# GarageDigitalClockDisplay.net
KiCad netlist of a schematic drawn in EAGLE
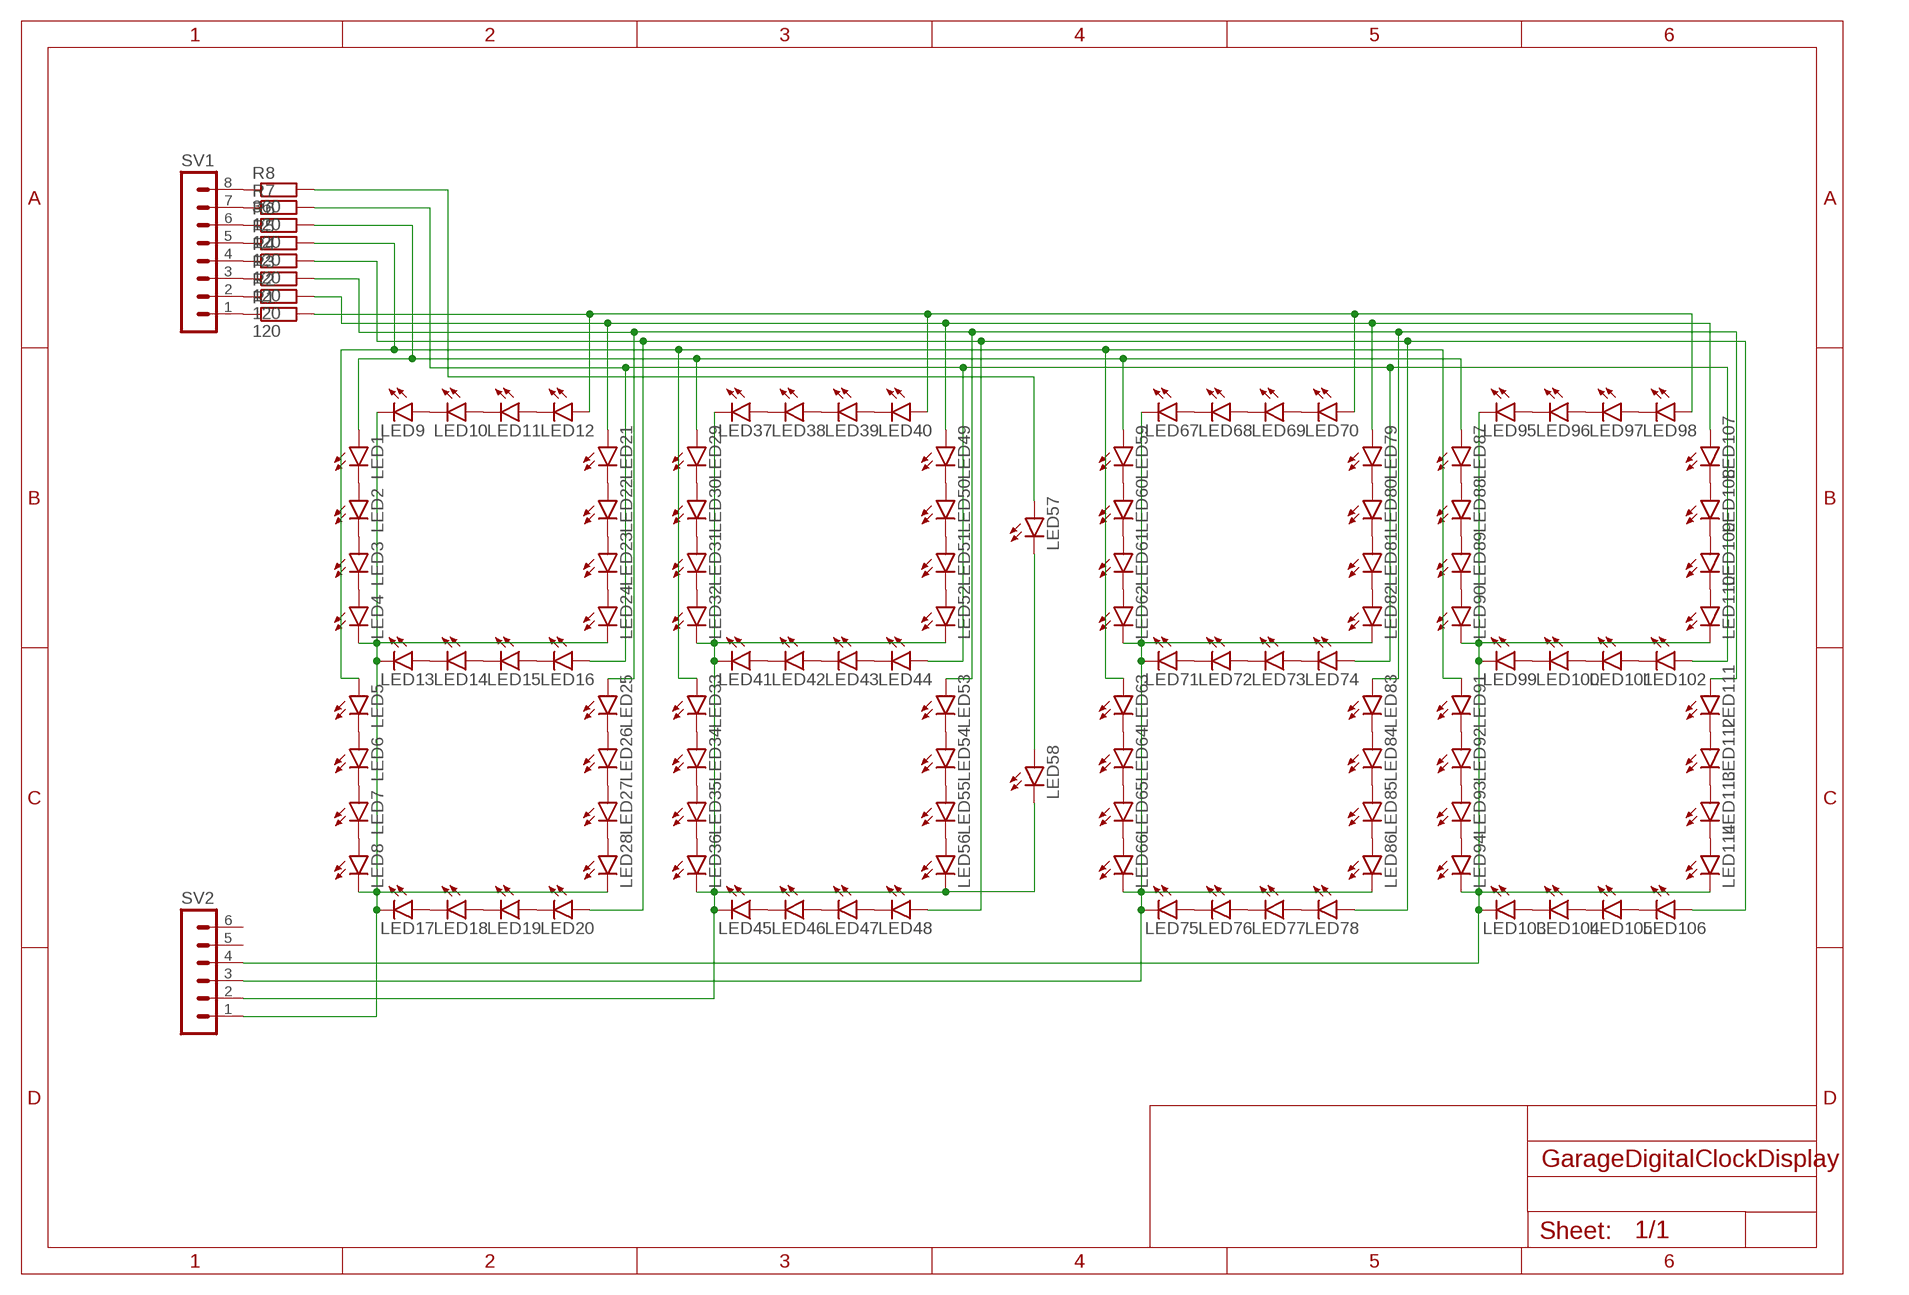
[diagram p0: schematic, sheet 1]

(export (version "E")
  (design (tool "Eeschema 10.0.6"))
  (components
    (comp (ref "LED1")
      (value "LED5MM")
      (footprint "eagle-import:LED5MM")
      (libsource (lib "eagle-import") (part "LED5MM"))
    )
    (comp (ref "LED2")
      (value "LED5MM")
      (footprint "eagle-import:LED5MM")
      (libsource (lib "eagle-import") (part "LED5MM"))
    )
    (comp (ref "LED3")
      (value "LED5MM")
      (footprint "eagle-import:LED5MM")
      (libsource (lib "eagle-import") (part "LED5MM"))
    )
    (comp (ref "LED4")
      (value "LED5MM")
      (footprint "eagle-import:LED5MM")
      (libsource (lib "eagle-import") (part "LED5MM"))
    )
    (comp (ref "LED5")
      (value "LED5MM")
      (footprint "eagle-import:LED5MM")
      (libsource (lib "eagle-import") (part "LED5MM"))
    )
    (comp (ref "LED6")
      (value "LED5MM")
      (footprint "eagle-import:LED5MM")
      (libsource (lib "eagle-import") (part "LED5MM"))
    )
    (comp (ref "LED7")
      (value "LED5MM")
      (footprint "eagle-import:LED5MM")
      (libsource (lib "eagle-import") (part "LED5MM"))
    )
    (comp (ref "LED8")
      (value "LED5MM")
      (footprint "eagle-import:LED5MM")
      (libsource (lib "eagle-import") (part "LED5MM"))
    )
    (comp (ref "LED9")
      (value "LED5MM")
      (footprint "eagle-import:LED5MM")
      (libsource (lib "eagle-import") (part "LED5MM"))
    )
    (comp (ref "LED10")
      (value "LED5MM")
      (footprint "eagle-import:LED5MM")
      (libsource (lib "eagle-import") (part "LED5MM"))
    )
    (comp (ref "LED11")
      (value "LED5MM")
      (footprint "eagle-import:LED5MM")
      (libsource (lib "eagle-import") (part "LED5MM"))
    )
    (comp (ref "LED12")
      (value "LED5MM")
      (footprint "eagle-import:LED5MM")
      (libsource (lib "eagle-import") (part "LED5MM"))
    )
    (comp (ref "LED13")
      (value "LED5MM")
      (footprint "eagle-import:LED5MM")
      (libsource (lib "eagle-import") (part "LED5MM"))
    )
    (comp (ref "LED14")
      (value "LED5MM")
      (footprint "eagle-import:LED5MM")
      (libsource (lib "eagle-import") (part "LED5MM"))
    )
    (comp (ref "LED15")
      (value "LED5MM")
      (footprint "eagle-import:LED5MM")
      (libsource (lib "eagle-import") (part "LED5MM"))
    )
    (comp (ref "LED16")
      (value "LED5MM")
      (footprint "eagle-import:LED5MM")
      (libsource (lib "eagle-import") (part "LED5MM"))
    )
    (comp (ref "LED17")
      (value "LED5MM")
      (footprint "eagle-import:LED5MM")
      (libsource (lib "eagle-import") (part "LED5MM"))
    )
    (comp (ref "LED18")
      (value "LED5MM")
      (footprint "eagle-import:LED5MM")
      (libsource (lib "eagle-import") (part "LED5MM"))
    )
    (comp (ref "LED19")
      (value "LED5MM")
      (footprint "eagle-import:LED5MM")
      (libsource (lib "eagle-import") (part "LED5MM"))
    )
    (comp (ref "LED20")
      (value "LED5MM")
      (footprint "eagle-import:LED5MM")
      (libsource (lib "eagle-import") (part "LED5MM"))
    )
    (comp (ref "LED21")
      (value "LED5MM")
      (footprint "eagle-import:LED5MM")
      (libsource (lib "eagle-import") (part "LED5MM"))
    )
    (comp (ref "LED22")
      (value "LED5MM")
      (footprint "eagle-import:LED5MM")
      (libsource (lib "eagle-import") (part "LED5MM"))
    )
    (comp (ref "LED23")
      (value "LED5MM")
      (footprint "eagle-import:LED5MM")
      (libsource (lib "eagle-import") (part "LED5MM"))
    )
    (comp (ref "LED24")
      (value "LED5MM")
      (footprint "eagle-import:LED5MM")
      (libsource (lib "eagle-import") (part "LED5MM"))
    )
    (comp (ref "LED25")
      (value "LED5MM")
      (footprint "eagle-import:LED5MM")
      (libsource (lib "eagle-import") (part "LED5MM"))
    )
    (comp (ref "LED26")
      (value "LED5MM")
      (footprint "eagle-import:LED5MM")
      (libsource (lib "eagle-import") (part "LED5MM"))
    )
    (comp (ref "LED27")
      (value "LED5MM")
      (footprint "eagle-import:LED5MM")
      (libsource (lib "eagle-import") (part "LED5MM"))
    )
    (comp (ref "LED28")
      (value "LED5MM")
      (footprint "eagle-import:LED5MM")
      (libsource (lib "eagle-import") (part "LED5MM"))
    )
    (comp (ref "LED29")
      (value "LED5MM")
      (footprint "eagle-import:LED5MM")
      (libsource (lib "eagle-import") (part "LED5MM"))
    )
    (comp (ref "LED30")
      (value "LED5MM")
      (footprint "eagle-import:LED5MM")
      (libsource (lib "eagle-import") (part "LED5MM"))
    )
    (comp (ref "LED31")
      (value "LED5MM")
      (footprint "eagle-import:LED5MM")
      (libsource (lib "eagle-import") (part "LED5MM"))
    )
    (comp (ref "LED32")
      (value "LED5MM")
      (footprint "eagle-import:LED5MM")
      (libsource (lib "eagle-import") (part "LED5MM"))
    )
    (comp (ref "LED33")
      (value "LED5MM")
      (footprint "eagle-import:LED5MM")
      (libsource (lib "eagle-import") (part "LED5MM"))
    )
    (comp (ref "LED34")
      (value "LED5MM")
      (footprint "eagle-import:LED5MM")
      (libsource (lib "eagle-import") (part "LED5MM"))
    )
    (comp (ref "LED35")
      (value "LED5MM")
      (footprint "eagle-import:LED5MM")
      (libsource (lib "eagle-import") (part "LED5MM"))
    )
    (comp (ref "LED36")
      (value "LED5MM")
      (footprint "eagle-import:LED5MM")
      (libsource (lib "eagle-import") (part "LED5MM"))
    )
    (comp (ref "LED37")
      (value "LED5MM")
      (footprint "eagle-import:LED5MM")
      (libsource (lib "eagle-import") (part "LED5MM"))
    )
    (comp (ref "LED38")
      (value "LED5MM")
      (footprint "eagle-import:LED5MM")
      (libsource (lib "eagle-import") (part "LED5MM"))
    )
    (comp (ref "LED39")
      (value "LED5MM")
      (footprint "eagle-import:LED5MM")
      (libsource (lib "eagle-import") (part "LED5MM"))
    )
    (comp (ref "LED40")
      (value "LED5MM")
      (footprint "eagle-import:LED5MM")
      (libsource (lib "eagle-import") (part "LED5MM"))
    )
    (comp (ref "LED41")
      (value "LED5MM")
      (footprint "eagle-import:LED5MM")
      (libsource (lib "eagle-import") (part "LED5MM"))
    )
    (comp (ref "LED42")
      (value "LED5MM")
      (footprint "eagle-import:LED5MM")
      (libsource (lib "eagle-import") (part "LED5MM"))
    )
    (comp (ref "LED43")
      (value "LED5MM")
      (footprint "eagle-import:LED5MM")
      (libsource (lib "eagle-import") (part "LED5MM"))
    )
    (comp (ref "LED44")
      (value "LED5MM")
      (footprint "eagle-import:LED5MM")
      (libsource (lib "eagle-import") (part "LED5MM"))
    )
    (comp (ref "LED45")
      (value "LED5MM")
      (footprint "eagle-import:LED5MM")
      (libsource (lib "eagle-import") (part "LED5MM"))
    )
    (comp (ref "LED46")
      (value "LED5MM")
      (footprint "eagle-import:LED5MM")
      (libsource (lib "eagle-import") (part "LED5MM"))
    )
    (comp (ref "LED47")
      (value "LED5MM")
      (footprint "eagle-import:LED5MM")
      (libsource (lib "eagle-import") (part "LED5MM"))
    )
    (comp (ref "LED48")
      (value "LED5MM")
      (footprint "eagle-import:LED5MM")
      (libsource (lib "eagle-import") (part "LED5MM"))
    )
    (comp (ref "LED49")
      (value "LED5MM")
      (footprint "eagle-import:LED5MM")
      (libsource (lib "eagle-import") (part "LED5MM"))
    )
    (comp (ref "LED50")
      (value "LED5MM")
      (footprint "eagle-import:LED5MM")
      (libsource (lib "eagle-import") (part "LED5MM"))
    )
    (comp (ref "LED51")
      (value "LED5MM")
      (footprint "eagle-import:LED5MM")
      (libsource (lib "eagle-import") (part "LED5MM"))
    )
    (comp (ref "LED52")
      (value "LED5MM")
      (footprint "eagle-import:LED5MM")
      (libsource (lib "eagle-import") (part "LED5MM"))
    )
    (comp (ref "LED53")
      (value "LED5MM")
      (footprint "eagle-import:LED5MM")
      (libsource (lib "eagle-import") (part "LED5MM"))
    )
    (comp (ref "LED54")
      (value "LED5MM")
      (footprint "eagle-import:LED5MM")
      (libsource (lib "eagle-import") (part "LED5MM"))
    )
    (comp (ref "LED55")
      (value "LED5MM")
      (footprint "eagle-import:LED5MM")
      (libsource (lib "eagle-import") (part "LED5MM"))
    )
    (comp (ref "LED56")
      (value "LED5MM")
      (footprint "eagle-import:LED5MM")
      (libsource (lib "eagle-import") (part "LED5MM"))
    )
    (comp (ref "LED57")
      (value "LED5MM")
      (footprint "eagle-import:LED5MM")
      (libsource (lib "eagle-import") (part "LED5MM"))
    )
    (comp (ref "LED58")
      (value "LED5MM")
      (footprint "eagle-import:LED5MM")
      (libsource (lib "eagle-import") (part "LED5MM"))
    )
    (comp (ref "LED59")
      (value "LED5MM")
      (footprint "eagle-import:LED5MM")
      (libsource (lib "eagle-import") (part "LED5MM"))
    )
    (comp (ref "LED60")
      (value "LED5MM")
      (footprint "eagle-import:LED5MM")
      (libsource (lib "eagle-import") (part "LED5MM"))
    )
    (comp (ref "LED61")
      (value "LED5MM")
      (footprint "eagle-import:LED5MM")
      (libsource (lib "eagle-import") (part "LED5MM"))
    )
    (comp (ref "LED62")
      (value "LED5MM")
      (footprint "eagle-import:LED5MM")
      (libsource (lib "eagle-import") (part "LED5MM"))
    )
    (comp (ref "LED63")
      (value "LED5MM")
      (footprint "eagle-import:LED5MM")
      (libsource (lib "eagle-import") (part "LED5MM"))
    )
    (comp (ref "LED64")
      (value "LED5MM")
      (footprint "eagle-import:LED5MM")
      (libsource (lib "eagle-import") (part "LED5MM"))
    )
    (comp (ref "LED65")
      (value "LED5MM")
      (footprint "eagle-import:LED5MM")
      (libsource (lib "eagle-import") (part "LED5MM"))
    )
    (comp (ref "LED66")
      (value "LED5MM")
      (footprint "eagle-import:LED5MM")
      (libsource (lib "eagle-import") (part "LED5MM"))
    )
    (comp (ref "LED67")
      (value "LED5MM")
      (footprint "eagle-import:LED5MM")
      (libsource (lib "eagle-import") (part "LED5MM"))
    )
    (comp (ref "LED68")
      (value "LED5MM")
      (footprint "eagle-import:LED5MM")
      (libsource (lib "eagle-import") (part "LED5MM"))
    )
    (comp (ref "LED69")
      (value "LED5MM")
      (footprint "eagle-import:LED5MM")
      (libsource (lib "eagle-import") (part "LED5MM"))
    )
    (comp (ref "LED70")
      (value "LED5MM")
      (footprint "eagle-import:LED5MM")
      (libsource (lib "eagle-import") (part "LED5MM"))
    )
    (comp (ref "LED71")
      (value "LED5MM")
      (footprint "eagle-import:LED5MM")
      (libsource (lib "eagle-import") (part "LED5MM"))
    )
    (comp (ref "LED72")
      (value "LED5MM")
      (footprint "eagle-import:LED5MM")
      (libsource (lib "eagle-import") (part "LED5MM"))
    )
    (comp (ref "LED73")
      (value "LED5MM")
      (footprint "eagle-import:LED5MM")
      (libsource (lib "eagle-import") (part "LED5MM"))
    )
    (comp (ref "LED74")
      (value "LED5MM")
      (footprint "eagle-import:LED5MM")
      (libsource (lib "eagle-import") (part "LED5MM"))
    )
    (comp (ref "LED75")
      (value "LED5MM")
      (footprint "eagle-import:LED5MM")
      (libsource (lib "eagle-import") (part "LED5MM"))
    )
    (comp (ref "LED76")
      (value "LED5MM")
      (footprint "eagle-import:LED5MM")
      (libsource (lib "eagle-import") (part "LED5MM"))
    )
    (comp (ref "LED77")
      (value "LED5MM")
      (footprint "eagle-import:LED5MM")
      (libsource (lib "eagle-import") (part "LED5MM"))
    )
    (comp (ref "LED78")
      (value "LED5MM")
      (footprint "eagle-import:LED5MM")
      (libsource (lib "eagle-import") (part "LED5MM"))
    )
    (comp (ref "LED79")
      (value "LED5MM")
      (footprint "eagle-import:LED5MM")
      (libsource (lib "eagle-import") (part "LED5MM"))
    )
    (comp (ref "LED80")
      (value "LED5MM")
      (footprint "eagle-import:LED5MM")
      (libsource (lib "eagle-import") (part "LED5MM"))
    )
    (comp (ref "LED81")
      (value "LED5MM")
      (footprint "eagle-import:LED5MM")
      (libsource (lib "eagle-import") (part "LED5MM"))
    )
    (comp (ref "LED82")
      (value "LED5MM")
      (footprint "eagle-import:LED5MM")
      (libsource (lib "eagle-import") (part "LED5MM"))
    )
    (comp (ref "LED83")
      (value "LED5MM")
      (footprint "eagle-import:LED5MM")
      (libsource (lib "eagle-import") (part "LED5MM"))
    )
    (comp (ref "LED84")
      (value "LED5MM")
      (footprint "eagle-import:LED5MM")
      (libsource (lib "eagle-import") (part "LED5MM"))
    )
    (comp (ref "LED85")
      (value "LED5MM")
      (footprint "eagle-import:LED5MM")
      (libsource (lib "eagle-import") (part "LED5MM"))
    )
    (comp (ref "LED86")
      (value "LED5MM")
      (footprint "eagle-import:LED5MM")
      (libsource (lib "eagle-import") (part "LED5MM"))
    )
    (comp (ref "LED87")
      (value "LED5MM")
      (footprint "eagle-import:LED5MM")
      (libsource (lib "eagle-import") (part "LED5MM"))
    )
    (comp (ref "LED88")
      (value "LED5MM")
      (footprint "eagle-import:LED5MM")
      (libsource (lib "eagle-import") (part "LED5MM"))
    )
    (comp (ref "LED89")
      (value "LED5MM")
      (footprint "eagle-import:LED5MM")
      (libsource (lib "eagle-import") (part "LED5MM"))
    )
    (comp (ref "LED90")
      (value "LED5MM")
      (footprint "eagle-import:LED5MM")
      (libsource (lib "eagle-import") (part "LED5MM"))
    )
    (comp (ref "LED91")
      (value "LED5MM")
      (footprint "eagle-import:LED5MM")
      (libsource (lib "eagle-import") (part "LED5MM"))
    )
    (comp (ref "LED92")
      (value "LED5MM")
      (footprint "eagle-import:LED5MM")
      (libsource (lib "eagle-import") (part "LED5MM"))
    )
    (comp (ref "LED93")
      (value "LED5MM")
      (footprint "eagle-import:LED5MM")
      (libsource (lib "eagle-import") (part "LED5MM"))
    )
    (comp (ref "LED94")
      (value "LED5MM")
      (footprint "eagle-import:LED5MM")
      (libsource (lib "eagle-import") (part "LED5MM"))
    )
    (comp (ref "LED95")
      (value "LED5MM")
      (footprint "eagle-import:LED5MM")
      (libsource (lib "eagle-import") (part "LED5MM"))
    )
    (comp (ref "LED96")
      (value "LED5MM")
      (footprint "eagle-import:LED5MM")
      (libsource (lib "eagle-import") (part "LED5MM"))
    )
    (comp (ref "LED97")
      (value "LED5MM")
      (footprint "eagle-import:LED5MM")
      (libsource (lib "eagle-import") (part "LED5MM"))
    )
    (comp (ref "LED98")
      (value "LED5MM")
      (footprint "eagle-import:LED5MM")
      (libsource (lib "eagle-import") (part "LED5MM"))
    )
    (comp (ref "LED99")
      (value "LED5MM")
      (footprint "eagle-import:LED5MM")
      (libsource (lib "eagle-import") (part "LED5MM"))
    )
    (comp (ref "LED100")
      (value "LED5MM")
      (footprint "eagle-import:LED5MM")
      (libsource (lib "eagle-import") (part "LED5MM"))
    )
    (comp (ref "LED101")
      (value "LED5MM")
      (footprint "eagle-import:LED5MM")
      (libsource (lib "eagle-import") (part "LED5MM"))
    )
    (comp (ref "LED102")
      (value "LED5MM")
      (footprint "eagle-import:LED5MM")
      (libsource (lib "eagle-import") (part "LED5MM"))
    )
    (comp (ref "LED103")
      (value "LED5MM")
      (footprint "eagle-import:LED5MM")
      (libsource (lib "eagle-import") (part "LED5MM"))
    )
    (comp (ref "LED104")
      (value "LED5MM")
      (footprint "eagle-import:LED5MM")
      (libsource (lib "eagle-import") (part "LED5MM"))
    )
    (comp (ref "LED105")
      (value "LED5MM")
      (footprint "eagle-import:LED5MM")
      (libsource (lib "eagle-import") (part "LED5MM"))
    )
    (comp (ref "LED106")
      (value "LED5MM")
      (footprint "eagle-import:LED5MM")
      (libsource (lib "eagle-import") (part "LED5MM"))
    )
    (comp (ref "LED107")
      (value "LED5MM")
      (footprint "eagle-import:LED5MM")
      (libsource (lib "eagle-import") (part "LED5MM"))
    )
    (comp (ref "LED108")
      (value "LED5MM")
      (footprint "eagle-import:LED5MM")
      (libsource (lib "eagle-import") (part "LED5MM"))
    )
    (comp (ref "LED109")
      (value "LED5MM")
      (footprint "eagle-import:LED5MM")
      (libsource (lib "eagle-import") (part "LED5MM"))
    )
    (comp (ref "LED110")
      (value "LED5MM")
      (footprint "eagle-import:LED5MM")
      (libsource (lib "eagle-import") (part "LED5MM"))
    )
    (comp (ref "LED111")
      (value "LED5MM")
      (footprint "eagle-import:LED5MM")
      (libsource (lib "eagle-import") (part "LED5MM"))
    )
    (comp (ref "LED112")
      (value "LED5MM")
      (footprint "eagle-import:LED5MM")
      (libsource (lib "eagle-import") (part "LED5MM"))
    )
    (comp (ref "LED113")
      (value "LED5MM")
      (footprint "eagle-import:LED5MM")
      (libsource (lib "eagle-import") (part "LED5MM"))
    )
    (comp (ref "LED114")
      (value "LED5MM")
      (footprint "eagle-import:LED5MM")
      (libsource (lib "eagle-import") (part "LED5MM"))
    )
    (comp (ref "R1")
      (value "120")
      (footprint "eagle-import:0207_10")
      (libsource (lib "eagle-import") (part "R-EU_0207/10"))
    )
    (comp (ref "R2")
      (value "120")
      (footprint "eagle-import:0207_10")
      (libsource (lib "eagle-import") (part "R-EU_0207/10"))
    )
    (comp (ref "R3")
      (value "120")
      (footprint "eagle-import:0207_10")
      (libsource (lib "eagle-import") (part "R-EU_0207/10"))
    )
    (comp (ref "R4")
      (value "120")
      (footprint "eagle-import:0207_10")
      (libsource (lib "eagle-import") (part "R-EU_0207/10"))
    )
    (comp (ref "R5")
      (value "120")
      (footprint "eagle-import:0207_10")
      (libsource (lib "eagle-import") (part "R-EU_0207/10"))
    )
    (comp (ref "R6")
      (value "120")
      (footprint "eagle-import:0207_10")
      (libsource (lib "eagle-import") (part "R-EU_0207/10"))
    )
    (comp (ref "R7")
      (value "120")
      (footprint "eagle-import:0207_10")
      (libsource (lib "eagle-import") (part "R-EU_0207/10"))
    )
    (comp (ref "R8")
      (value "360")
      (footprint "eagle-import:0207_10")
      (libsource (lib "eagle-import") (part "R-EU_0207/10"))
    )
    (comp (ref "SV1")
      (value "MA08-1")
      (footprint "eagle-import:MA08-1")
      (libsource (lib "eagle-import") (part "MA08-1"))
    )
    (comp (ref "SV2")
      (value "MA06-1")
      (footprint "eagle-import:MA06-1")
      (libsource (lib "eagle-import") (part "MA06-1"))
    )
  )
  (nets
    (net (code "1") (name "Net-(LED1-C)") (class "Default")
      (node (ref "LED1") (pin "K") (pinfunction "C_K") (pintype "passive"))
      (node (ref "LED2") (pin "A") (pinfunction "A_A") (pintype "passive"))
    )
    (net (code "2") (name "Net-(LED1-PadA)") (class "Default")
      (node (ref "LED1") (pin "A") (pinfunction "A_A") (pintype "passive"))
      (node (ref "LED29") (pin "A") (pinfunction "A_A") (pintype "passive"))
      (node (ref "LED59") (pin "A") (pinfunction "A_A") (pintype "passive"))
      (node (ref "LED87") (pin "A") (pinfunction "A_A") (pintype "passive"))
      (node (ref "R6") (pin "2") (pinfunction "2_2") (pintype "passive"))
    )
    (net (code "3") (name "Net-(LED2-C)") (class "Default")
      (node (ref "LED2") (pin "K") (pinfunction "C_K") (pintype "passive"))
      (node (ref "LED3") (pin "A") (pinfunction "A_A") (pintype "passive"))
    )
    (net (code "4") (name "Net-(LED3-C)") (class "Default")
      (node (ref "LED3") (pin "K") (pinfunction "C_K") (pintype "passive"))
      (node (ref "LED4") (pin "A") (pinfunction "A_A") (pintype "passive"))
    )
    (net (code "5") (name "Net-(LED5-C)") (class "Default")
      (node (ref "LED5") (pin "K") (pinfunction "C_K") (pintype "passive"))
      (node (ref "LED6") (pin "A") (pinfunction "A_A") (pintype "passive"))
    )
    (net (code "6") (name "Net-(LED6-C)") (class "Default")
      (node (ref "LED6") (pin "K") (pinfunction "C_K") (pintype "passive"))
      (node (ref "LED7") (pin "A") (pinfunction "A_A") (pintype "passive"))
    )
    (net (code "7") (name "Net-(LED7-C)") (class "Default")
      (node (ref "LED7") (pin "K") (pinfunction "C_K") (pintype "passive"))
      (node (ref "LED8") (pin "A") (pinfunction "A_A") (pintype "passive"))
    )
    (net (code "8") (name "Net-(LED10-C)") (class "Default")
      (node (ref "LED10") (pin "K") (pinfunction "C_K") (pintype "passive"))
      (node (ref "LED9") (pin "A") (pinfunction "A_A") (pintype "passive"))
    )
    (net (code "9") (name "Net-(LED11-C)") (class "Default")
      (node (ref "LED10") (pin "A") (pinfunction "A_A") (pintype "passive"))
      (node (ref "LED11") (pin "K") (pinfunction "C_K") (pintype "passive"))
    )
    (net (code "10") (name "Net-(LED12-C)") (class "Default")
      (node (ref "LED11") (pin "A") (pinfunction "A_A") (pintype "passive"))
      (node (ref "LED12") (pin "K") (pinfunction "C_K") (pintype "passive"))
    )
    (net (code "11") (name "Net-(LED12-PadA)") (class "Default")
      (node (ref "LED12") (pin "A") (pinfunction "A_A") (pintype "passive"))
      (node (ref "LED40") (pin "A") (pinfunction "A_A") (pintype "passive"))
      (node (ref "LED70") (pin "A") (pinfunction "A_A") (pintype "passive"))
      (node (ref "LED98") (pin "A") (pinfunction "A_A") (pintype "passive"))
      (node (ref "R1") (pin "2") (pinfunction "2_2") (pintype "passive"))
    )
    (net (code "12") (name "Net-(LED13-C)") (class "Default")
      (node (ref "LED13") (pin "K") (pinfunction "C_K") (pintype "passive"))
      (node (ref "LED17") (pin "K") (pinfunction "C_K") (pintype "passive"))
      (node (ref "LED24") (pin "K") (pinfunction "C_K") (pintype "passive"))
      (node (ref "LED28") (pin "K") (pinfunction "C_K") (pintype "passive"))
      (node (ref "LED4") (pin "K") (pinfunction "C_K") (pintype "passive"))
      (node (ref "LED8") (pin "K") (pinfunction "C_K") (pintype "passive"))
      (node (ref "LED9") (pin "K") (pinfunction "C_K") (pintype "passive"))
      (node (ref "SV2") (pin "1") (pinfunction "1_1") (pintype "passive"))
    )
    (net (code "13") (name "Net-(LED14-C)") (class "Default")
      (node (ref "LED13") (pin "A") (pinfunction "A_A") (pintype "passive"))
      (node (ref "LED14") (pin "K") (pinfunction "C_K") (pintype "passive"))
    )
    (net (code "14") (name "Net-(LED15-C)") (class "Default")
      (node (ref "LED14") (pin "A") (pinfunction "A_A") (pintype "passive"))
      (node (ref "LED15") (pin "K") (pinfunction "C_K") (pintype "passive"))
    )
    (net (code "15") (name "Net-(LED16-C)") (class "Default")
      (node (ref "LED15") (pin "A") (pinfunction "A_A") (pintype "passive"))
      (node (ref "LED16") (pin "K") (pinfunction "C_K") (pintype "passive"))
    )
    (net (code "16") (name "Net-(LED18-C)") (class "Default")
      (node (ref "LED17") (pin "A") (pinfunction "A_A") (pintype "passive"))
      (node (ref "LED18") (pin "K") (pinfunction "C_K") (pintype "passive"))
    )
    (net (code "17") (name "Net-(LED19-C)") (class "Default")
      (node (ref "LED18") (pin "A") (pinfunction "A_A") (pintype "passive"))
      (node (ref "LED19") (pin "K") (pinfunction "C_K") (pintype "passive"))
    )
    (net (code "18") (name "Net-(LED20-C)") (class "Default")
      (node (ref "LED19") (pin "A") (pinfunction "A_A") (pintype "passive"))
      (node (ref "LED20") (pin "K") (pinfunction "C_K") (pintype "passive"))
    )
    (net (code "19") (name "Net-(LED21-C)") (class "Default")
      (node (ref "LED21") (pin "K") (pinfunction "C_K") (pintype "passive"))
      (node (ref "LED22") (pin "A") (pinfunction "A_A") (pintype "passive"))
    )
    (net (code "20") (name "Net-(LED22-C)") (class "Default")
      (node (ref "LED22") (pin "K") (pinfunction "C_K") (pintype "passive"))
      (node (ref "LED23") (pin "A") (pinfunction "A_A") (pintype "passive"))
    )
    (net (code "21") (name "Net-(LED23-C)") (class "Default")
      (node (ref "LED23") (pin "K") (pinfunction "C_K") (pintype "passive"))
      (node (ref "LED24") (pin "A") (pinfunction "A_A") (pintype "passive"))
    )
    (net (code "22") (name "Net-(LED25-C)") (class "Default")
      (node (ref "LED25") (pin "K") (pinfunction "C_K") (pintype "passive"))
      (node (ref "LED26") (pin "A") (pinfunction "A_A") (pintype "passive"))
    )
    (net (code "23") (name "Net-(LED26-C)") (class "Default")
      (node (ref "LED26") (pin "K") (pinfunction "C_K") (pintype "passive"))
      (node (ref "LED27") (pin "A") (pinfunction "A_A") (pintype "passive"))
    )
    (net (code "24") (name "Net-(LED27-C)") (class "Default")
      (node (ref "LED27") (pin "K") (pinfunction "C_K") (pintype "passive"))
      (node (ref "LED28") (pin "A") (pinfunction "A_A") (pintype "passive"))
    )
    (net (code "25") (name "Net-(LED29-C)") (class "Default")
      (node (ref "LED29") (pin "K") (pinfunction "C_K") (pintype "passive"))
      (node (ref "LED30") (pin "A") (pinfunction "A_A") (pintype "passive"))
    )
    (net (code "26") (name "Net-(LED30-C)") (class "Default")
      (node (ref "LED30") (pin "K") (pinfunction "C_K") (pintype "passive"))
      (node (ref "LED31") (pin "A") (pinfunction "A_A") (pintype "passive"))
    )
    (net (code "27") (name "Net-(LED31-C)") (class "Default")
      (node (ref "LED31") (pin "K") (pinfunction "C_K") (pintype "passive"))
      (node (ref "LED32") (pin "A") (pinfunction "A_A") (pintype "passive"))
    )
    (net (code "28") (name "Net-(LED32-C)") (class "Default")
      (node (ref "LED32") (pin "K") (pinfunction "C_K") (pintype "passive"))
      (node (ref "LED36") (pin "K") (pinfunction "C_K") (pintype "passive"))
      (node (ref "LED37") (pin "K") (pinfunction "C_K") (pintype "passive"))
      (node (ref "LED41") (pin "K") (pinfunction "C_K") (pintype "passive"))
      (node (ref "LED45") (pin "K") (pinfunction "C_K") (pintype "passive"))
      (node (ref "LED52") (pin "K") (pinfunction "C_K") (pintype "passive"))
      (node (ref "LED56") (pin "K") (pinfunction "C_K") (pintype "passive"))
      (node (ref "LED58") (pin "K") (pinfunction "C_K") (pintype "passive"))
      (node (ref "SV2") (pin "2") (pinfunction "2_2") (pintype "passive"))
    )
    (net (code "29") (name "Net-(LED33-C)") (class "Default")
      (node (ref "LED33") (pin "K") (pinfunction "C_K") (pintype "passive"))
      (node (ref "LED34") (pin "A") (pinfunction "A_A") (pintype "passive"))
    )
    (net (code "30") (name "Net-(LED33-PadA)") (class "Default")
      (node (ref "LED33") (pin "A") (pinfunction "A_A") (pintype "passive"))
      (node (ref "LED5") (pin "A") (pinfunction "A_A") (pintype "passive"))
      (node (ref "LED63") (pin "A") (pinfunction "A_A") (pintype "passive"))
      (node (ref "LED91") (pin "A") (pinfunction "A_A") (pintype "passive"))
      (node (ref "R5") (pin "2") (pinfunction "2_2") (pintype "passive"))
    )
    (net (code "31") (name "Net-(LED34-C)") (class "Default")
      (node (ref "LED34") (pin "K") (pinfunction "C_K") (pintype "passive"))
      (node (ref "LED35") (pin "A") (pinfunction "A_A") (pintype "passive"))
    )
    (net (code "32") (name "Net-(LED35-C)") (class "Default")
      (node (ref "LED35") (pin "K") (pinfunction "C_K") (pintype "passive"))
      (node (ref "LED36") (pin "A") (pinfunction "A_A") (pintype "passive"))
    )
    (net (code "33") (name "Net-(LED38-C)") (class "Default")
      (node (ref "LED37") (pin "A") (pinfunction "A_A") (pintype "passive"))
      (node (ref "LED38") (pin "K") (pinfunction "C_K") (pintype "passive"))
    )
    (net (code "34") (name "Net-(LED39-C)") (class "Default")
      (node (ref "LED38") (pin "A") (pinfunction "A_A") (pintype "passive"))
      (node (ref "LED39") (pin "K") (pinfunction "C_K") (pintype "passive"))
    )
    (net (code "35") (name "Net-(LED40-C)") (class "Default")
      (node (ref "LED39") (pin "A") (pinfunction "A_A") (pintype "passive"))
      (node (ref "LED40") (pin "K") (pinfunction "C_K") (pintype "passive"))
    )
    (net (code "36") (name "Net-(LED42-C)") (class "Default")
      (node (ref "LED41") (pin "A") (pinfunction "A_A") (pintype "passive"))
      (node (ref "LED42") (pin "K") (pinfunction "C_K") (pintype "passive"))
    )
    (net (code "37") (name "Net-(LED43-C)") (class "Default")
      (node (ref "LED42") (pin "A") (pinfunction "A_A") (pintype "passive"))
      (node (ref "LED43") (pin "K") (pinfunction "C_K") (pintype "passive"))
    )
    (net (code "38") (name "Net-(LED44-C)") (class "Default")
      (node (ref "LED43") (pin "A") (pinfunction "A_A") (pintype "passive"))
      (node (ref "LED44") (pin "K") (pinfunction "C_K") (pintype "passive"))
    )
    (net (code "39") (name "Net-(LED46-C)") (class "Default")
      (node (ref "LED45") (pin "A") (pinfunction "A_A") (pintype "passive"))
      (node (ref "LED46") (pin "K") (pinfunction "C_K") (pintype "passive"))
    )
    (net (code "40") (name "Net-(LED47-C)") (class "Default")
      (node (ref "LED46") (pin "A") (pinfunction "A_A") (pintype "passive"))
      (node (ref "LED47") (pin "K") (pinfunction "C_K") (pintype "passive"))
    )
    (net (code "41") (name "Net-(LED48-C)") (class "Default")
      (node (ref "LED47") (pin "A") (pinfunction "A_A") (pintype "passive"))
      (node (ref "LED48") (pin "K") (pinfunction "C_K") (pintype "passive"))
    )
    (net (code "42") (name "Net-(LED49-C)") (class "Default")
      (node (ref "LED49") (pin "K") (pinfunction "C_K") (pintype "passive"))
      (node (ref "LED50") (pin "A") (pinfunction "A_A") (pintype "passive"))
    )
    (net (code "43") (name "Net-(LED50-C)") (class "Default")
      (node (ref "LED50") (pin "K") (pinfunction "C_K") (pintype "passive"))
      (node (ref "LED51") (pin "A") (pinfunction "A_A") (pintype "passive"))
    )
    (net (code "44") (name "Net-(LED51-C)") (class "Default")
      (node (ref "LED51") (pin "K") (pinfunction "C_K") (pintype "passive"))
      (node (ref "LED52") (pin "A") (pinfunction "A_A") (pintype "passive"))
    )
    (net (code "45") (name "Net-(LED53-C)") (class "Default")
      (node (ref "LED53") (pin "K") (pinfunction "C_K") (pintype "passive"))
      (node (ref "LED54") (pin "A") (pinfunction "A_A") (pintype "passive"))
    )
    (net (code "46") (name "Net-(LED54-C)") (class "Default")
      (node (ref "LED54") (pin "K") (pinfunction "C_K") (pintype "passive"))
      (node (ref "LED55") (pin "A") (pinfunction "A_A") (pintype "passive"))
    )
    (net (code "47") (name "Net-(LED55-C)") (class "Default")
      (node (ref "LED55") (pin "K") (pinfunction "C_K") (pintype "passive"))
      (node (ref "LED56") (pin "A") (pinfunction "A_A") (pintype "passive"))
    )
    (net (code "48") (name "Net-(LED57-C)") (class "Default")
      (node (ref "LED57") (pin "K") (pinfunction "C_K") (pintype "passive"))
      (node (ref "LED58") (pin "A") (pinfunction "A_A") (pintype "passive"))
    )
    (net (code "49") (name "Net-(LED57-PadA)") (class "Default")
      (node (ref "LED57") (pin "A") (pinfunction "A_A") (pintype "passive"))
      (node (ref "R8") (pin "2") (pinfunction "2_2") (pintype "passive"))
    )
    (net (code "50") (name "Net-(LED59-C)") (class "Default")
      (node (ref "LED59") (pin "K") (pinfunction "C_K") (pintype "passive"))
      (node (ref "LED60") (pin "A") (pinfunction "A_A") (pintype "passive"))
    )
    (net (code "51") (name "Net-(LED60-C)") (class "Default")
      (node (ref "LED60") (pin "K") (pinfunction "C_K") (pintype "passive"))
      (node (ref "LED61") (pin "A") (pinfunction "A_A") (pintype "passive"))
    )
    (net (code "52") (name "Net-(LED61-C)") (class "Default")
      (node (ref "LED61") (pin "K") (pinfunction "C_K") (pintype "passive"))
      (node (ref "LED62") (pin "A") (pinfunction "A_A") (pintype "passive"))
    )
    (net (code "53") (name "Net-(LED62-C)") (class "Default")
      (node (ref "LED62") (pin "K") (pinfunction "C_K") (pintype "passive"))
      (node (ref "LED66") (pin "K") (pinfunction "C_K") (pintype "passive"))
      (node (ref "LED67") (pin "K") (pinfunction "C_K") (pintype "passive"))
      (node (ref "LED71") (pin "K") (pinfunction "C_K") (pintype "passive"))
      (node (ref "LED75") (pin "K") (pinfunction "C_K") (pintype "passive"))
      (node (ref "LED82") (pin "K") (pinfunction "C_K") (pintype "passive"))
      (node (ref "LED86") (pin "K") (pinfunction "C_K") (pintype "passive"))
      (node (ref "SV2") (pin "3") (pinfunction "3_3") (pintype "passive"))
    )
    (net (code "54") (name "Net-(LED63-C)") (class "Default")
      (node (ref "LED63") (pin "K") (pinfunction "C_K") (pintype "passive"))
      (node (ref "LED64") (pin "A") (pinfunction "A_A") (pintype "passive"))
    )
    (net (code "55") (name "Net-(LED64-C)") (class "Default")
      (node (ref "LED64") (pin "K") (pinfunction "C_K") (pintype "passive"))
      (node (ref "LED65") (pin "A") (pinfunction "A_A") (pintype "passive"))
    )
    (net (code "56") (name "Net-(LED65-C)") (class "Default")
      (node (ref "LED65") (pin "K") (pinfunction "C_K") (pintype "passive"))
      (node (ref "LED66") (pin "A") (pinfunction "A_A") (pintype "passive"))
    )
    (net (code "57") (name "Net-(LED68-C)") (class "Default")
      (node (ref "LED67") (pin "A") (pinfunction "A_A") (pintype "passive"))
      (node (ref "LED68") (pin "K") (pinfunction "C_K") (pintype "passive"))
    )
    (net (code "58") (name "Net-(LED69-C)") (class "Default")
      (node (ref "LED68") (pin "A") (pinfunction "A_A") (pintype "passive"))
      (node (ref "LED69") (pin "K") (pinfunction "C_K") (pintype "passive"))
    )
    (net (code "59") (name "Net-(LED70-C)") (class "Default")
      (node (ref "LED69") (pin "A") (pinfunction "A_A") (pintype "passive"))
      (node (ref "LED70") (pin "K") (pinfunction "C_K") (pintype "passive"))
    )
    (net (code "60") (name "Net-(LED72-C)") (class "Default")
      (node (ref "LED71") (pin "A") (pinfunction "A_A") (pintype "passive"))
      (node (ref "LED72") (pin "K") (pinfunction "C_K") (pintype "passive"))
    )
    (net (code "61") (name "Net-(LED73-C)") (class "Default")
      (node (ref "LED72") (pin "A") (pinfunction "A_A") (pintype "passive"))
      (node (ref "LED73") (pin "K") (pinfunction "C_K") (pintype "passive"))
    )
    (net (code "62") (name "Net-(LED74-C)") (class "Default")
      (node (ref "LED73") (pin "A") (pinfunction "A_A") (pintype "passive"))
      (node (ref "LED74") (pin "K") (pinfunction "C_K") (pintype "passive"))
    )
    (net (code "63") (name "Net-(LED76-C)") (class "Default")
      (node (ref "LED75") (pin "A") (pinfunction "A_A") (pintype "passive"))
      (node (ref "LED76") (pin "K") (pinfunction "C_K") (pintype "passive"))
    )
    (net (code "64") (name "Net-(LED77-C)") (class "Default")
      (node (ref "LED76") (pin "A") (pinfunction "A_A") (pintype "passive"))
      (node (ref "LED77") (pin "K") (pinfunction "C_K") (pintype "passive"))
    )
    (net (code "65") (name "Net-(LED78-C)") (class "Default")
      (node (ref "LED77") (pin "A") (pinfunction "A_A") (pintype "passive"))
      (node (ref "LED78") (pin "K") (pinfunction "C_K") (pintype "passive"))
    )
    (net (code "66") (name "Net-(LED79-C)") (class "Default")
      (node (ref "LED79") (pin "K") (pinfunction "C_K") (pintype "passive"))
      (node (ref "LED80") (pin "A") (pinfunction "A_A") (pintype "passive"))
    )
    (net (code "67") (name "Net-(LED80-C)") (class "Default")
      (node (ref "LED80") (pin "K") (pinfunction "C_K") (pintype "passive"))
      (node (ref "LED81") (pin "A") (pinfunction "A_A") (pintype "passive"))
    )
    (net (code "68") (name "Net-(LED81-C)") (class "Default")
      (node (ref "LED81") (pin "K") (pinfunction "C_K") (pintype "passive"))
      (node (ref "LED82") (pin "A") (pinfunction "A_A") (pintype "passive"))
    )
    (net (code "69") (name "Net-(LED83-C)") (class "Default")
      (node (ref "LED83") (pin "K") (pinfunction "C_K") (pintype "passive"))
      (node (ref "LED84") (pin "A") (pinfunction "A_A") (pintype "passive"))
    )
    (net (code "70") (name "Net-(LED84-C)") (class "Default")
      (node (ref "LED84") (pin "K") (pinfunction "C_K") (pintype "passive"))
      (node (ref "LED85") (pin "A") (pinfunction "A_A") (pintype "passive"))
    )
    (net (code "71") (name "Net-(LED85-C)") (class "Default")
      (node (ref "LED85") (pin "K") (pinfunction "C_K") (pintype "passive"))
      (node (ref "LED86") (pin "A") (pinfunction "A_A") (pintype "passive"))
    )
    (net (code "72") (name "Net-(LED87-C)") (class "Default")
      (node (ref "LED87") (pin "K") (pinfunction "C_K") (pintype "passive"))
      (node (ref "LED88") (pin "A") (pinfunction "A_A") (pintype "passive"))
    )
    (net (code "73") (name "Net-(LED88-C)") (class "Default")
      (node (ref "LED88") (pin "K") (pinfunction "C_K") (pintype "passive"))
      (node (ref "LED89") (pin "A") (pinfunction "A_A") (pintype "passive"))
    )
    (net (code "74") (name "Net-(LED89-C)") (class "Default")
      (node (ref "LED89") (pin "K") (pinfunction "C_K") (pintype "passive"))
      (node (ref "LED90") (pin "A") (pinfunction "A_A") (pintype "passive"))
    )
    (net (code "75") (name "Net-(LED91-C)") (class "Default")
      (node (ref "LED91") (pin "K") (pinfunction "C_K") (pintype "passive"))
      (node (ref "LED92") (pin "A") (pinfunction "A_A") (pintype "passive"))
    )
    (net (code "76") (name "Net-(LED92-C)") (class "Default")
      (node (ref "LED92") (pin "K") (pinfunction "C_K") (pintype "passive"))
      (node (ref "LED93") (pin "A") (pinfunction "A_A") (pintype "passive"))
    )
    (net (code "77") (name "Net-(LED93-C)") (class "Default")
      (node (ref "LED93") (pin "K") (pinfunction "C_K") (pintype "passive"))
      (node (ref "LED94") (pin "A") (pinfunction "A_A") (pintype "passive"))
    )
    (net (code "78") (name "Net-(LED96-C)") (class "Default")
      (node (ref "LED95") (pin "A") (pinfunction "A_A") (pintype "passive"))
      (node (ref "LED96") (pin "K") (pinfunction "C_K") (pintype "passive"))
    )
    (net (code "79") (name "Net-(LED97-C)") (class "Default")
      (node (ref "LED96") (pin "A") (pinfunction "A_A") (pintype "passive"))
      (node (ref "LED97") (pin "K") (pinfunction "C_K") (pintype "passive"))
    )
    (net (code "80") (name "Net-(LED98-C)") (class "Default")
      (node (ref "LED97") (pin "A") (pinfunction "A_A") (pintype "passive"))
      (node (ref "LED98") (pin "K") (pinfunction "C_K") (pintype "passive"))
    )
    (net (code "81") (name "Net-(LED100-C)") (class "Default")
      (node (ref "LED100") (pin "K") (pinfunction "C_K") (pintype "passive"))
      (node (ref "LED99") (pin "A") (pinfunction "A_A") (pintype "passive"))
    )
    (net (code "82") (name "Net-(LED101-C)") (class "Default")
      (node (ref "LED100") (pin "A") (pinfunction "A_A") (pintype "passive"))
      (node (ref "LED101") (pin "K") (pinfunction "C_K") (pintype "passive"))
    )
    (net (code "83") (name "Net-(LED102-C)") (class "Default")
      (node (ref "LED101") (pin "A") (pinfunction "A_A") (pintype "passive"))
      (node (ref "LED102") (pin "K") (pinfunction "C_K") (pintype "passive"))
    )
    (net (code "84") (name "Net-(LED102-PadA)") (class "Default")
      (node (ref "LED102") (pin "A") (pinfunction "A_A") (pintype "passive"))
      (node (ref "LED16") (pin "A") (pinfunction "A_A") (pintype "passive"))
      (node (ref "LED44") (pin "A") (pinfunction "A_A") (pintype "passive"))
      (node (ref "LED74") (pin "A") (pinfunction "A_A") (pintype "passive"))
      (node (ref "R7") (pin "2") (pinfunction "2_2") (pintype "passive"))
    )
    (net (code "85") (name "Net-(LED103-C)") (class "Default")
      (node (ref "LED103") (pin "K") (pinfunction "C_K") (pintype "passive"))
      (node (ref "LED110") (pin "K") (pinfunction "C_K") (pintype "passive"))
      (node (ref "LED114") (pin "K") (pinfunction "C_K") (pintype "passive"))
      (node (ref "LED90") (pin "K") (pinfunction "C_K") (pintype "passive"))
      (node (ref "LED94") (pin "K") (pinfunction "C_K") (pintype "passive"))
      (node (ref "LED95") (pin "K") (pinfunction "C_K") (pintype "passive"))
      (node (ref "LED99") (pin "K") (pinfunction "C_K") (pintype "passive"))
      (node (ref "SV2") (pin "4") (pinfunction "4_4") (pintype "passive"))
    )
    (net (code "86") (name "Net-(LED104-C)") (class "Default")
      (node (ref "LED103") (pin "A") (pinfunction "A_A") (pintype "passive"))
      (node (ref "LED104") (pin "K") (pinfunction "C_K") (pintype "passive"))
    )
    (net (code "87") (name "Net-(LED105-C)") (class "Default")
      (node (ref "LED104") (pin "A") (pinfunction "A_A") (pintype "passive"))
      (node (ref "LED105") (pin "K") (pinfunction "C_K") (pintype "passive"))
    )
    (net (code "88") (name "Net-(LED106-C)") (class "Default")
      (node (ref "LED105") (pin "A") (pinfunction "A_A") (pintype "passive"))
      (node (ref "LED106") (pin "K") (pinfunction "C_K") (pintype "passive"))
    )
    (net (code "89") (name "Net-(LED106-PadA)") (class "Default")
      (node (ref "LED106") (pin "A") (pinfunction "A_A") (pintype "passive"))
      (node (ref "LED20") (pin "A") (pinfunction "A_A") (pintype "passive"))
      (node (ref "LED48") (pin "A") (pinfunction "A_A") (pintype "passive"))
      (node (ref "LED78") (pin "A") (pinfunction "A_A") (pintype "passive"))
      (node (ref "R4") (pin "2") (pinfunction "2_2") (pintype "passive"))
    )
    (net (code "90") (name "Net-(LED107-C)") (class "Default")
      (node (ref "LED107") (pin "K") (pinfunction "C_K") (pintype "passive"))
      (node (ref "LED108") (pin "A") (pinfunction "A_A") (pintype "passive"))
    )
    (net (code "91") (name "Net-(LED107-PadA)") (class "Default")
      (node (ref "LED107") (pin "A") (pinfunction "A_A") (pintype "passive"))
      (node (ref "LED21") (pin "A") (pinfunction "A_A") (pintype "passive"))
      (node (ref "LED49") (pin "A") (pinfunction "A_A") (pintype "passive"))
      (node (ref "LED79") (pin "A") (pinfunction "A_A") (pintype "passive"))
      (node (ref "R2") (pin "2") (pinfunction "2_2") (pintype "passive"))
    )
    (net (code "92") (name "Net-(LED108-C)") (class "Default")
      (node (ref "LED108") (pin "K") (pinfunction "C_K") (pintype "passive"))
      (node (ref "LED109") (pin "A") (pinfunction "A_A") (pintype "passive"))
    )
    (net (code "93") (name "Net-(LED109-C)") (class "Default")
      (node (ref "LED109") (pin "K") (pinfunction "C_K") (pintype "passive"))
      (node (ref "LED110") (pin "A") (pinfunction "A_A") (pintype "passive"))
    )
    (net (code "94") (name "Net-(LED111-C)") (class "Default")
      (node (ref "LED111") (pin "K") (pinfunction "C_K") (pintype "passive"))
      (node (ref "LED112") (pin "A") (pinfunction "A_A") (pintype "passive"))
    )
    (net (code "95") (name "Net-(LED111-PadA)") (class "Default")
      (node (ref "LED111") (pin "A") (pinfunction "A_A") (pintype "passive"))
      (node (ref "LED25") (pin "A") (pinfunction "A_A") (pintype "passive"))
      (node (ref "LED53") (pin "A") (pinfunction "A_A") (pintype "passive"))
      (node (ref "LED83") (pin "A") (pinfunction "A_A") (pintype "passive"))
      (node (ref "R3") (pin "2") (pinfunction "2_2") (pintype "passive"))
    )
    (net (code "96") (name "Net-(LED112-C)") (class "Default")
      (node (ref "LED112") (pin "K") (pinfunction "C_K") (pintype "passive"))
      (node (ref "LED113") (pin "A") (pinfunction "A_A") (pintype "passive"))
    )
    (net (code "97") (name "Net-(LED113-C)") (class "Default")
      (node (ref "LED113") (pin "K") (pinfunction "C_K") (pintype "passive"))
      (node (ref "LED114") (pin "A") (pinfunction "A_A") (pintype "passive"))
    )
    (net (code "98") (name "Net-(R1-Pad1)") (class "Default")
      (node (ref "R1") (pin "1") (pinfunction "1_1") (pintype "passive"))
      (node (ref "SV1") (pin "1") (pinfunction "1_1") (pintype "passive"))
    )
    (net (code "99") (name "Net-(R2-Pad1)") (class "Default")
      (node (ref "R2") (pin "1") (pinfunction "1_1") (pintype "passive"))
      (node (ref "SV1") (pin "2") (pinfunction "2_2") (pintype "passive"))
    )
    (net (code "100") (name "Net-(R3-Pad1)") (class "Default")
      (node (ref "R3") (pin "1") (pinfunction "1_1") (pintype "passive"))
      (node (ref "SV1") (pin "3") (pinfunction "3_3") (pintype "passive"))
    )
    (net (code "101") (name "Net-(R4-Pad1)") (class "Default")
      (node (ref "R4") (pin "1") (pinfunction "1_1") (pintype "passive"))
      (node (ref "SV1") (pin "4") (pinfunction "4_4") (pintype "passive"))
    )
    (net (code "102") (name "Net-(R5-Pad1)") (class "Default")
      (node (ref "R5") (pin "1") (pinfunction "1_1") (pintype "passive"))
      (node (ref "SV1") (pin "5") (pinfunction "5_5") (pintype "passive"))
    )
    (net (code "103") (name "Net-(R6-Pad1)") (class "Default")
      (node (ref "R6") (pin "1") (pinfunction "1_1") (pintype "passive"))
      (node (ref "SV1") (pin "6") (pinfunction "6_6") (pintype "passive"))
    )
    (net (code "104") (name "Net-(R7-Pad1)") (class "Default")
      (node (ref "R7") (pin "1") (pinfunction "1_1") (pintype "passive"))
      (node (ref "SV1") (pin "7") (pinfunction "7_7") (pintype "passive"))
    )
    (net (code "105") (name "Net-(R8-Pad1)") (class "Default")
      (node (ref "R8") (pin "1") (pinfunction "1_1") (pintype "passive"))
      (node (ref "SV1") (pin "8") (pinfunction "8_8") (pintype "passive"))
    )
    (net (code "106") (name "unconnected-(SV2-Pad5)") (class "Default")
      (node (ref "SV2") (pin "5") (pinfunction "5_5") (pintype "passive"))
    )
    (net (code "107") (name "unconnected-(SV2-Pad6)") (class "Default")
      (node (ref "SV2") (pin "6") (pinfunction "6_6") (pintype "passive"))
    )
  )
)
